# Kernal2.net
KiCad netlist of a schematic drawn in Altium Designer
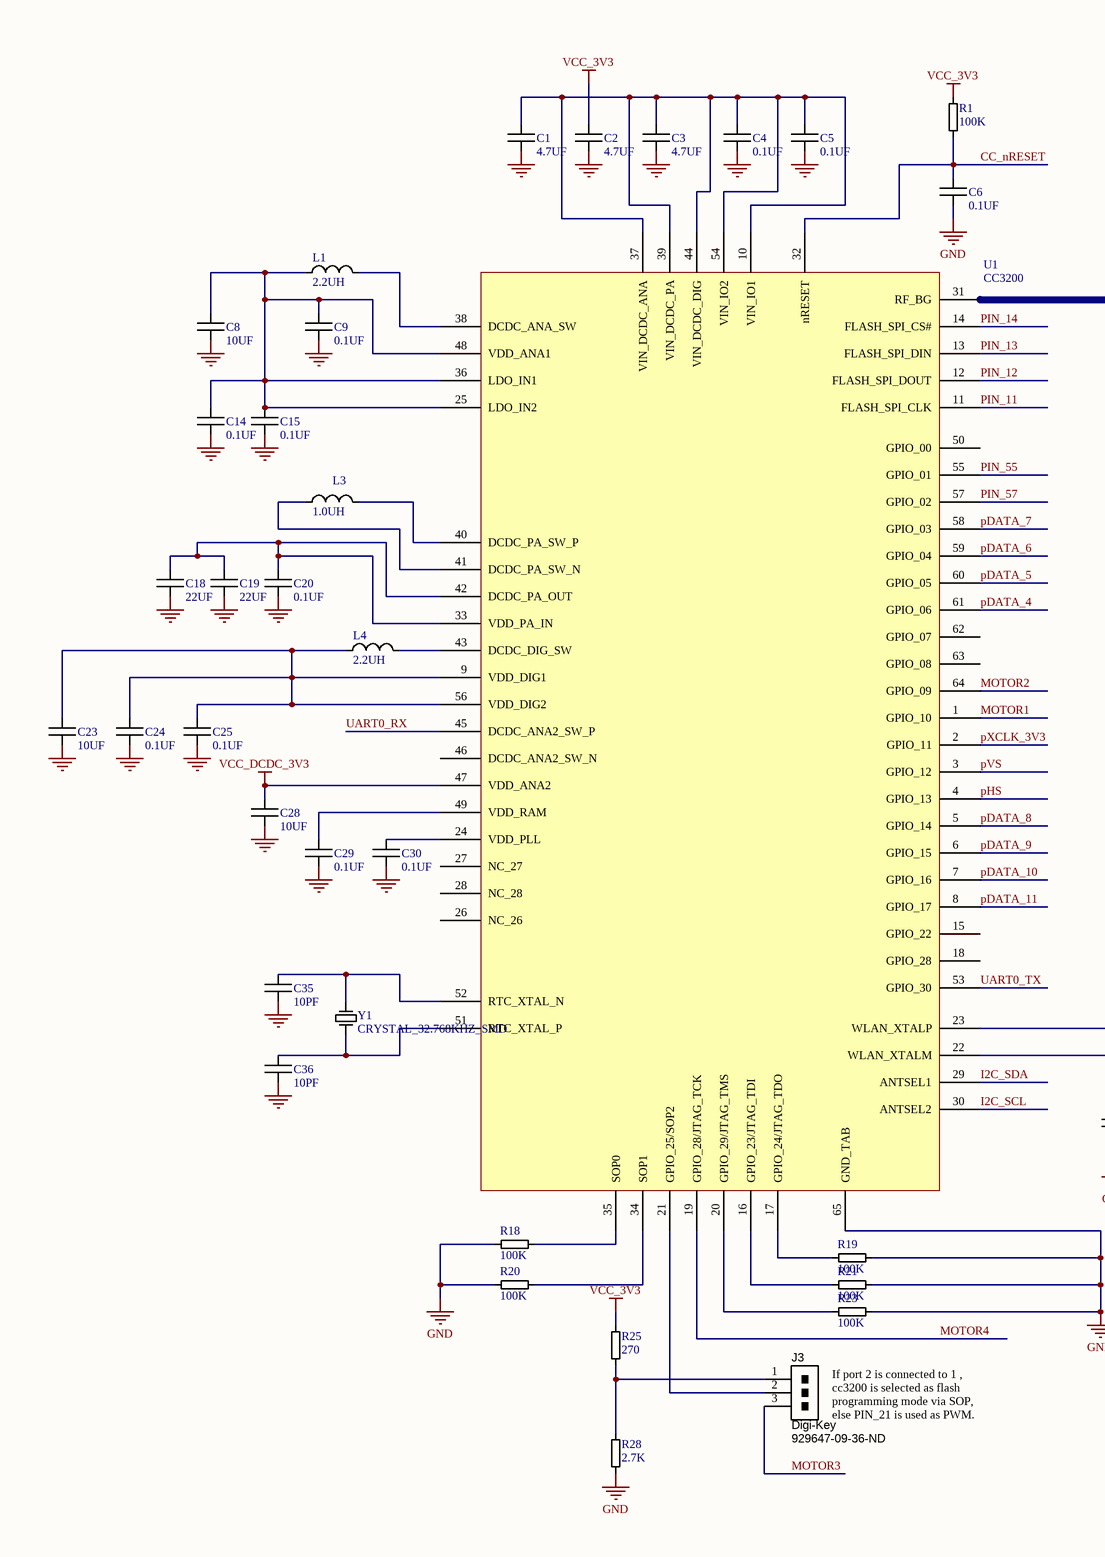
[diagram p0: Kernal2.SchDoc, left]
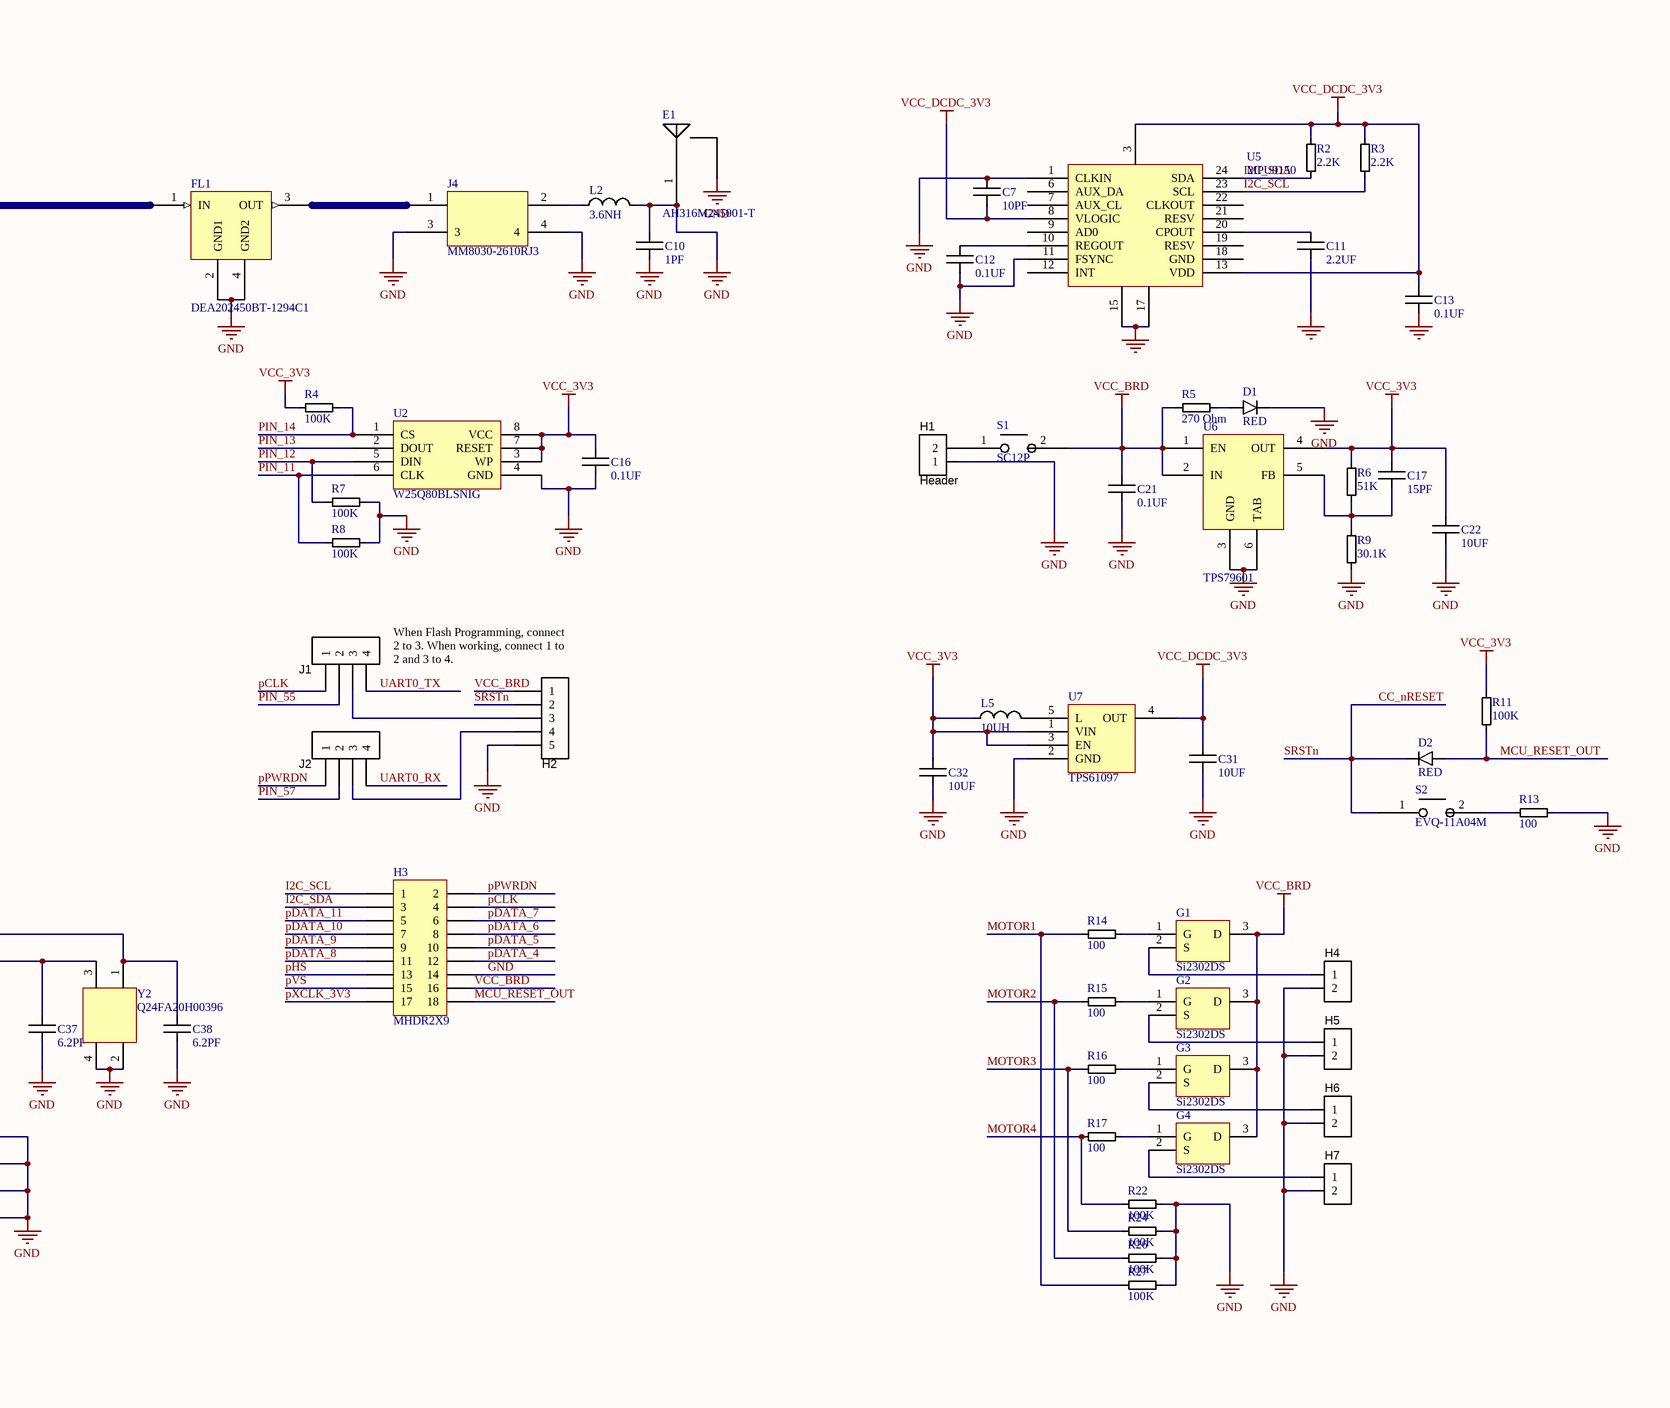
[diagram p1: Kernal2.SchDoc, right]

(export (version "E")
  (design (tool "Eeschema 10.0.6"))
  (components
    (comp (ref "C1")
      (value "4.7UF")
      (footprint "0402")
      (description "CAP CER 4.7UF 6.3V 20% X5R 0402")
      (libsource (lib "FuzzyWasp") (part "CAP_0402"))
    )
    (comp (ref "C2") (value "4.7UF") (footprint "0402") (libsource (lib "FuzzyWasp") (part "CAP_0402")))
    (comp (ref "C3") (value "4.7UF") (footprint "0402") (libsource (lib "FuzzyWasp") (part "CAP_0402")))
    (comp (ref "C4")
      (value "0.1UF")
      (footprint "0402")
      (description "CAP CER 0.1UF 10V 10% X5R 0402")
      (libsource (lib "FuzzyWasp") (part "CAP_0402"))
    )
    (comp (ref "C5")
      (value "0.1UF")
      (footprint "0402")
      (description "CAP CER 0.1UF 10V 10% X5R 0402")
      (libsource (lib "FuzzyWasp") (part "CAP_0402"))
    )
    (comp (ref "C6")
      (value "0.1UF")
      (footprint "0402")
      (description "CAP CER 0.1UF 10V 10% X5R 0402")
      (libsource (lib "FuzzyWasp") (part "CAP_0402"))
    )
    (comp (ref "C7")
      (value "10PF")
      (footprint "0402")
      (description "CAP CER 10PF 50V NP0 0402")
      (libsource (lib "FuzzyWasp") (part "CAP_0402"))
    )
    (comp (ref "C8")
      (value "10UF")
      (footprint "0402")
      (description "CAP CER 10UF 6.3V 20% X5R 0603")
      (libsource (lib "FuzzyWasp") (part "CAP_0402"))
    )
    (comp (ref "C9")
      (value "0.1UF")
      (footprint "0402")
      (description "CAP CER 0.1UF 10V 10% X5R 0402")
      (libsource (lib "FuzzyWasp") (part "CAP_0402"))
    )
    (comp (ref "C10")
      (value "1PF")
      (footprint "0402")
      (description "CAP CER 1PF 50V NP0 0402")
      (libsource (lib "FuzzyWasp") (part "CAP_0402"))
    )
    (comp (ref "C11")
      (value "2.2UF")
      (footprint "0402")
      (description "CAP CER 2.2UF 10V 10% X5R 0402")
      (libsource (lib "FuzzyWasp") (part "CAP_0402"))
    )
    (comp (ref "C12")
      (value "0.1UF")
      (footprint "0402")
      (description "CAP CER 0.1UF 10V 10% X5R 0402")
      (libsource (lib "FuzzyWasp") (part "CAP_0402"))
    )
    (comp (ref "C13")
      (value "0.1UF")
      (footprint "0402")
      (description "CAP CER 0.1UF 10V 10% X5R 0402")
      (libsource (lib "FuzzyWasp") (part "CAP_0402"))
    )
    (comp (ref "C14")
      (value "0.1UF")
      (footprint "0402")
      (description "CAP CER 0.1UF 10V 10% X5R 0402")
      (libsource (lib "FuzzyWasp") (part "CAP_0402"))
    )
    (comp (ref "C15")
      (value "0.1UF")
      (footprint "0402")
      (description "CAP CER 0.1UF 10V 10% X5R 0402")
      (libsource (lib "FuzzyWasp") (part "CAP_0402"))
    )
    (comp (ref "C16")
      (value "0.1UF")
      (footprint "0402")
      (description "CAP CER 0.1UF 10V 10% X5R 0402")
      (libsource (lib "FuzzyWasp") (part "CAP_0402"))
    )
    (comp (ref "C17")
      (value "15PF")
      (footprint "0402")
      (description "CAP CER 15PF 50V 5% NP0 0402")
      (libsource (lib "FuzzyWasp") (part "CAP_0402"))
    )
    (comp (ref "C18")
      (value "22UF")
      (footprint "0603")
      (description "CAP CER 22UF 4V 20% X5R 0603")
      (libsource (lib "FuzzyWasp") (part "CAP_0603"))
    )
    (comp (ref "C19")
      (value "22UF")
      (footprint "0603")
      (description "CAP CER 22UF 4V 20% X5R 0603")
      (libsource (lib "FuzzyWasp") (part "CAP_0603"))
    )
    (comp (ref "C20")
      (value "0.1UF")
      (footprint "0402")
      (description "CAP CER 0.1UF 10V 10% X5R 0402")
      (libsource (lib "FuzzyWasp") (part "CAP_0402"))
    )
    (comp (ref "C21")
      (value "0.1UF")
      (footprint "0402")
      (description "CAP CER 0.1UF 10V 10% X5R 0402")
      (libsource (lib "FuzzyWasp") (part "CAP_0402"))
    )
    (comp (ref "C22")
      (value "10UF")
      (footprint "0805")
      (description "CAP CER 10UF 10V 10% X5R 0805")
      (libsource (lib "FuzzyWasp") (part "CAP_0805"))
    )
    (comp (ref "C23")
      (value "10UF")
      (footprint "0603")
      (description "CAP CER 10UF 6.3V 20% X5R 0603")
      (libsource (lib "FuzzyWasp") (part "CAP_0603"))
    )
    (comp (ref "C24")
      (value "0.1UF")
      (footprint "0402")
      (description "CAP CER 0.1UF 10V 10% X5R 0402")
      (libsource (lib "FuzzyWasp") (part "CAP_0402"))
    )
    (comp (ref "C25")
      (value "0.1UF")
      (footprint "0402")
      (description "CAP CER 0.1UF 10V 10% X5R 0402")
      (libsource (lib "FuzzyWasp") (part "CAP_0402"))
    )
    (comp (ref "C28")
      (value "10UF")
      (footprint "0603")
      (description "CAP CER 10UF 6.3V 20% X5R 0603")
      (libsource (lib "FuzzyWasp") (part "CAP_0603"))
    )
    (comp (ref "C29")
      (value "0.1UF")
      (footprint "0402")
      (description "CAP CER 0.1UF 10V 10% X5R 0402")
      (libsource (lib "FuzzyWasp") (part "CAP_0402"))
    )
    (comp (ref "C30")
      (value "0.1UF")
      (footprint "0402")
      (description "CAP CER 0.1UF 10V 10% X5R 0402")
      (libsource (lib "FuzzyWasp") (part "CAP_0402"))
    )
    (comp (ref "C31")
      (value "10UF")
      (footprint "0603")
      (description "CAP CER 10UF 6.3V 20% X5R 0603")
      (libsource (lib "FuzzyWasp") (part "CAP_0603"))
    )
    (comp (ref "C32")
      (value "10UF")
      (footprint "0603")
      (description "CAP CER 10UF 6.3V 20% X5R 0603")
      (libsource (lib "FuzzyWasp") (part "CAP_0603"))
    )
    (comp (ref "C35")
      (value "10PF")
      (footprint "0402")
      (description "CAP CER 10PF 50V 1% NP0 0402")
      (libsource (lib "FuzzyWasp") (part "CAP_0402"))
    )
    (comp (ref "C36")
      (value "10PF")
      (footprint "0402")
      (description "CAP CER 10PF 50V 1% NP0 0402")
      (libsource (lib "FuzzyWasp") (part "CAP_0402"))
    )
    (comp (ref "C37")
      (value "6.2PF")
      (footprint "0402")
      (description "CAP CER 6.2PF 50V NP0 0402")
      (libsource (lib "FuzzyWasp") (part "CAP_0402"))
    )
    (comp (ref "C38")
      (value "6.2PF")
      (footprint "0402")
      (description "CAP CER 6.2PF 50V NP0 0402")
      (libsource (lib "FuzzyWasp") (part "CAP_0402"))
    )
    (comp (ref "D1")
      (value "RED")
      (footprint "0603")
      (description "LED CHIPLED 633NM RED 0603 SMD")
      (libsource (lib "FuzzyWasp") (part "LED_0603"))
    )
    (comp (ref "D2")
      (value "RED")
      (footprint "0603")
      (description "LED CHIPLED 633NM RED 0603 SMD")
      (libsource (lib "FuzzyWasp") (part "LED_0603"))
    )
    (comp (ref "E1")
      (value "AH316M245001-T")
      (footprint "AH316M245001-T")
      (libsource (lib "FuzzyWasp-2") (part "AH316M245001-T"))
    )
    (comp (ref "FL1")
      (value "DEA202450BT-1294C1")
      (footprint "DEA202450BT-1294C1-H")
      (libsource (lib "FuzzyWasp-2") (part "DEA202450BT-1294C1"))
    )
    (comp (ref "G1")
      (value "Si2302DS")
      (footprint "Si2302DS")
      (libsource (lib "FuzzyWasp-2") (part "Si2302DS"))
    )
    (comp (ref "G2")
      (value "Si2302DS")
      (footprint "Si2302DS")
      (libsource (lib "FuzzyWasp-2") (part "Si2302DS"))
    )
    (comp (ref "G3")
      (value "Si2302DS")
      (footprint "Si2302DS")
      (libsource (lib "FuzzyWasp-2") (part "Si2302DS"))
    )
    (comp (ref "G4")
      (value "Si2302DS")
      (footprint "Si2302DS")
      (libsource (lib "FuzzyWasp-2") (part "Si2302DS"))
    )
    (comp (ref "H1")
      (value "Header")
      (footprint "MHDR1X2")
      (description "Header, 2-pin")
      (libsource (lib "PBL - Connectors") (part "Header2P"))
    )
    (comp (ref "H2")
      (value "Programmer")
      (footprint "MHDR1X5")
      (description "Header 5-pin")
      (libsource (lib "PBL - Connectors") (part "Header5P"))
    )
    (comp (ref "H3")
      (value "MHDR2X9")
      (footprint "MHDR2X9")
      (description "Header, 9-Pin, Dual row")
      (fields (field (name "PUBLISHER") "Altium Limited"))
      (libsource (lib "Miscellaneous Connectors") (part "MHDR2X9"))
    )
    (comp (ref "H4")
      (value "Header")
      (footprint "MHDR1X2")
      (description "Header, 2-pin")
      (libsource (lib "") (part "Header2P_1"))
    )
    (comp (ref "H5")
      (value "Header")
      (footprint "MHDR1X2")
      (description "Header, 2-pin")
      (libsource (lib "") (part "Header2P_1"))
    )
    (comp (ref "H6")
      (value "Header")
      (footprint "MHDR1X2")
      (description "Header, 2-pin")
      (libsource (lib "") (part "Header2P_1"))
    )
    (comp (ref "H7")
      (value "Header")
      (footprint "MHDR1X2")
      (description "Header, 2-pin")
      (libsource (lib "") (part "Header2P_1"))
    )
    (comp (ref "J1")
      (value "Programmer")
      (footprint "MHDR1X4")
      (description "Header 4-pin")
      (libsource (lib "PBL - Connectors") (part "Header4P"))
    )
    (comp (ref "J2")
      (value "Programmer")
      (footprint "MHDR1X4")
      (description "Header 4-pin")
      (libsource (lib "PBL - Connectors") (part "Header4P"))
    )
    (comp (ref "J3")
      (value "CONN_HEADER_1x3P_0.100in")
      (footprint "MHDR1X3")
      (description "Pin Header, THT, Single-row, 2.54mm pitch")
      (fields
        (field (name "SUPPLIER 1") "Digi-Key")
        (field (name "SUPPLIER PART NUMBER 1") "929647-09-36-ND")
      )
      (libsource (lib "PBL - Connectors") (part "CONN_HEADER_1x3P_0.100in"))
    )
    (comp (ref "J4")
      (value "MM8030-2610RJ3")
      (footprint "MM8030-2610RJ3")
      (libsource (lib "FuzzyWasp-2") (part "MM8030-2610RJ3"))
    )
    (comp (ref "L1")
      (value "2.2UH")
      (footprint "1008")
      (description "INDUCTOR 2.2UH 20% 1300MA 1008")
      (libsource (lib "FuzzyWasp") (part "INDUCTOR_1008"))
    )
    (comp (ref "L2")
      (value "3.6NH")
      (footprint "0402")
      (description "INDUCTOR 3.6NH 0.1NH 0402")
      (libsource (lib "FuzzyWasp") (part "INDUCTOR_0402"))
    )
    (comp (ref "L3")
      (value "1.0UH")
      (footprint "1007")
      (description "INDUCTOR POWER 1.0UH 1007")
      (libsource (lib "FuzzyWasp") (part "INDUCTOR_1007"))
    )
    (comp (ref "L4")
      (value "2.2UH")
      (footprint "1008")
      (description "INDUCTOR 2.2UH 20% 1300MA 1008")
      (libsource (lib "FuzzyWasp") (part "INDUCTOR_1008"))
    )
    (comp (ref "L5")
      (value "10UH")
      (footprint "1007")
      (description "INDUCTOR POWER 10UH 1007")
      (libsource (lib "FuzzyWasp") (part "INDUCTOR_1007"))
    )
    (comp (ref "R1")
      (value "100K")
      (footprint "0402")
      (description "RES 100K OHM 1/16W 5% 0402 SMD")
      (libsource (lib "FuzzyWasp") (part "RES_0402"))
    )
    (comp (ref "R2")
      (value "2.2K")
      (footprint "0402")
      (description "RES 2.2K OHM 1/10W 5% 0402 SMD")
      (libsource (lib "FuzzyWasp") (part "RES_0402"))
    )
    (comp (ref "R3")
      (value "2.2K")
      (footprint "0402")
      (description "RES 2.2K OHM 1/10W 5% 0402 SMD")
      (libsource (lib "FuzzyWasp") (part "RES_0402"))
    )
    (comp (ref "R4")
      (value "100K")
      (footprint "0402")
      (description "RES 100K OHM 1/16W 5% 0402 SMD")
      (libsource (lib "FuzzyWasp") (part "RES_0402"))
    )
    (comp (ref "R5")
      (value "270 Ohm")
      (footprint "0402")
      (description "RES 270 OHM 1/10W 5% 0603 SMD")
      (libsource (lib "FuzzyWasp") (part "RES_0402"))
    )
    (comp (ref "R6")
      (value "51K")
      (footprint "0402")
      (description "RES 51K OHM 1/16W 1% 0402")
      (libsource (lib "FuzzyWasp") (part "RES_0402"))
    )
    (comp (ref "R7")
      (value "100K")
      (footprint "0402")
      (description "RES 100K OHM 1/16W 5% 0402 SMD")
      (libsource (lib "FuzzyWasp") (part "RES_0402"))
    )
    (comp (ref "R8")
      (value "100K")
      (footprint "0402")
      (description "RES 100K OHM 1/16W 5% 0402 SMD")
      (libsource (lib "FuzzyWasp") (part "RES_0402"))
    )
    (comp (ref "R9")
      (value "30.1K")
      (footprint "0402")
      (description "RES 30.1K OHM 1/16W 1% 0402 SMD")
      (libsource (lib "FuzzyWasp") (part "RES_0402"))
    )
    (comp (ref "R11")
      (value "100K")
      (footprint "0402")
      (description "RES 100K OHM 1/16W 5% 0402 SMD")
      (libsource (lib "FuzzyWasp") (part "RES_0402"))
    )
    (comp (ref "R13")
      (value "100")
      (footprint "0402")
      (description "RES 100 OHM 1/10W 5% 0402 SMD")
      (libsource (lib "FuzzyWasp") (part "RES_0402"))
    )
    (comp (ref "R14")
      (value "100")
      (footprint "0402")
      (description "RES 100 OHM 1/10W 5% 0402 SMD")
      (libsource (lib "FuzzyWasp") (part "RES_0402"))
    )
    (comp (ref "R15")
      (value "100")
      (footprint "0402")
      (description "RES 100 OHM 1/10W 5% 0402 SMD")
      (libsource (lib "FuzzyWasp") (part "RES_0402"))
    )
    (comp (ref "R16")
      (value "100")
      (footprint "0402")
      (description "RES 100 OHM 1/10W 5% 0402 SMD")
      (libsource (lib "FuzzyWasp") (part "RES_0402"))
    )
    (comp (ref "R17")
      (value "100")
      (footprint "0402")
      (description "RES 100 OHM 1/10W 5% 0402 SMD")
      (libsource (lib "FuzzyWasp") (part "RES_0402"))
    )
    (comp (ref "R18")
      (value "100K")
      (footprint "0402")
      (description "RES 100K OHM 1/16W 5% 0402 SMD")
      (libsource (lib "FuzzyWasp") (part "RES_0402"))
    )
    (comp (ref "R19")
      (value "100K")
      (footprint "0402")
      (description "RES 100K OHM 1/16W 5% 0402 SMD")
      (libsource (lib "FuzzyWasp") (part "RES_0402"))
    )
    (comp (ref "R20")
      (value "100K")
      (footprint "0402")
      (description "RES 100K OHM 1/16W 5% 0402 SMD")
      (libsource (lib "FuzzyWasp") (part "RES_0402"))
    )
    (comp (ref "R21")
      (value "100K")
      (footprint "0402")
      (description "RES 100K OHM 1/16W 5% 0402 SMD")
      (libsource (lib "FuzzyWasp") (part "RES_0402"))
    )
    (comp (ref "R22")
      (value "100K")
      (footprint "0402")
      (description "RES 100K OHM 1/16W 5% 0402 SMD")
      (libsource (lib "FuzzyWasp") (part "RES_0402"))
    )
    (comp (ref "R23")
      (value "100K")
      (footprint "0402")
      (description "RES 100K OHM 1/16W 5% 0402 SMD")
      (libsource (lib "FuzzyWasp") (part "RES_0402"))
    )
    (comp (ref "R24")
      (value "100K")
      (footprint "0402")
      (description "RES 100K OHM 1/16W 5% 0402 SMD")
      (libsource (lib "FuzzyWasp") (part "RES_0402"))
    )
    (comp (ref "R25")
      (value "270")
      (footprint "0402")
      (description "RES 270 OHM 1/16W 1% 0402 SMD")
      (libsource (lib "FuzzyWasp") (part "RES_0402"))
    )
    (comp (ref "R26")
      (value "100K")
      (footprint "0402")
      (description "RES 100K OHM 1/16W 5% 0402 SMD")
      (libsource (lib "FuzzyWasp") (part "RES_0402"))
    )
    (comp (ref "R27")
      (value "100K")
      (footprint "0402")
      (description "RES 100K OHM 1/16W 5% 0402 SMD")
      (libsource (lib "FuzzyWasp") (part "RES_0402"))
    )
    (comp (ref "R28")
      (value "2.7K")
      (footprint "0402")
      (description "RES 2.70K OHM 1/16W 1% 0402 SMD")
      (libsource (lib "FuzzyWasp") (part "RES_0402"))
    )
    (comp (ref "S1") (value "SC12P") (footprint "SC12P") (libsource (lib "FuzzyWasp") (part "SC12P")))
    (comp (ref "S2")
      (value "EVQ-11A04M")
      (footprint "EVQ-11")
      (libsource (lib "FuzzyWasp") (part "EVQ-11A04M"))
    )
    (comp (ref "U1") (value "CC3200") (footprint "CC3200") (libsource (lib "FuzzyWasp-2") (part "CC3200")))
    (comp (ref "U2")
      (value "W25Q80BLSNIG")
      (footprint "W25Q80BLSNIG")
      (libsource (lib "FuzzyWasp-2") (part "W25Q80BLSNIG"))
    )
    (comp (ref "U5") (value "MPU9150") (footprint "MPU9150") (libsource (lib "FuzzyWasp-2") (part "MPU9150")))
    (comp (ref "U6")
      (value "TPS79601")
      (footprint "TPS79601")
      (libsource (lib "FuzzyWasp-2") (part "TPS79601"))
    )
    (comp (ref "U7")
      (value "TPS61097")
      (footprint "TPS61097A-33")
      (libsource (lib "FuzzyWasp-2") (part "TPS61097"))
    )
    (comp (ref "Y1")
      (value "CRYSTAL_32.768KHZ_SMD")
      (footprint "ABS07")
      (libsource (lib "FuzzyWasp-2") (part "CRYSTAL_32.768KHZ_SMD"))
    )
    (comp (ref "Y2") (value "Q24FA20H00396") (libsource (lib "FuzzyWasp-2") (part "Q24FA20H00396")))
  )
  (nets
    (net (code "1") (name "/CC_nRESET") (class "Default")
      (node (ref "C6") (pin "2") (pinfunction "2_2") (pintype "passive"))
      (node (ref "D2") (pin "2") (pinfunction "2_2") (pintype "passive"))
      (node (ref "H2") (pin "2") (pinfunction "2_2") (pintype "passive"))
      (node (ref "R1") (pin "1") (pinfunction "1_1") (pintype "passive"))
      (node (ref "S2") (pin "1") (pinfunction "1_1") (pintype "passive"))
      (node (ref "U1") (pin "32") (pinfunction "nRESET_32") (pintype "passive"))
    )
    (net (code "2") (name "/I2C_SCL") (class "Default")
      (node (ref "H3") (pin "1") (pinfunction "1_1") (pintype "passive"))
      (node (ref "R3") (pin "1") (pinfunction "1_1") (pintype "passive"))
      (node (ref "U1") (pin "30") (pinfunction "ANTSEL2_30") (pintype "passive"))
      (node (ref "U5") (pin "23") (pinfunction "SCL_23") (pintype "passive"))
    )
    (net (code "3") (name "/I2C_SDA") (class "Default")
      (node (ref "H3") (pin "3") (pinfunction "3_3") (pintype "passive"))
      (node (ref "R2") (pin "1") (pinfunction "1_1") (pintype "passive"))
      (node (ref "U1") (pin "29") (pinfunction "ANTSEL1_29") (pintype "passive"))
      (node (ref "U5") (pin "24") (pinfunction "SDA_24") (pintype "passive"))
    )
    (net (code "4") (name "/MCU_RESET_OUT") (class "Default")
      (node (ref "D2") (pin "1") (pinfunction "1_1") (pintype "passive"))
      (node (ref "H3") (pin "18") (pinfunction "18_18") (pintype "passive"))
      (node (ref "R11") (pin "1") (pinfunction "1_1") (pintype "passive"))
    )
    (net (code "5") (name "/MOTOR1") (class "Default")
      (node (ref "R14") (pin "1") (pinfunction "1_1") (pintype "passive"))
      (node (ref "R27") (pin "1") (pinfunction "1_1") (pintype "passive"))
      (node (ref "U1") (pin "1") (pinfunction "GPIO_10_1") (pintype "passive"))
    )
    (net (code "6") (name "/MOTOR2") (class "Default")
      (node (ref "R15") (pin "1") (pinfunction "1_1") (pintype "passive"))
      (node (ref "R26") (pin "1") (pinfunction "1_1") (pintype "passive"))
      (node (ref "U1") (pin "64") (pinfunction "GPIO_09_64") (pintype "passive"))
    )
    (net (code "7") (name "/MOTOR3") (class "Default")
      (node (ref "J3") (pin "3") (pinfunction "3_3") (pintype "passive"))
      (node (ref "R16") (pin "1") (pinfunction "1_1") (pintype "passive"))
      (node (ref "R24") (pin "1") (pinfunction "1_1") (pintype "passive"))
    )
    (net (code "8") (name "/MOTOR4") (class "Default")
      (node (ref "R17") (pin "1") (pinfunction "1_1") (pintype "passive"))
      (node (ref "R22") (pin "1") (pinfunction "1_1") (pintype "passive"))
      (node (ref "U1") (pin "19") (pinfunction "GPIO_28/JTAG_TCK_19") (pintype "passive"))
    )
    (net (code "9") (name "/PIN_11") (class "Default")
      (node (ref "R8") (pin "1") (pinfunction "1_1") (pintype "passive"))
      (node (ref "U1") (pin "11") (pinfunction "FLASH_SPI_CLK_11") (pintype "passive"))
      (node (ref "U2") (pin "6") (pinfunction "CLK_6") (pintype "passive"))
    )
    (net (code "10") (name "/PIN_12") (class "Default")
      (node (ref "R7") (pin "1") (pinfunction "1_1") (pintype "passive"))
      (node (ref "U1") (pin "12") (pinfunction "FLASH_SPI_DOUT_12") (pintype "passive"))
      (node (ref "U2") (pin "5") (pinfunction "DIN_5") (pintype "passive"))
    )
    (net (code "11") (name "/PIN_13") (class "Default")
      (node (ref "U1") (pin "13") (pinfunction "FLASH_SPI_DIN_13") (pintype "passive"))
      (node (ref "U2") (pin "2") (pinfunction "DOUT_2") (pintype "passive"))
    )
    (net (code "12") (name "/PIN_14") (class "Default")
      (node (ref "R4") (pin "2") (pinfunction "2_2") (pintype "passive"))
      (node (ref "U1") (pin "14") (pinfunction "FLASH_SPI_CS#_14") (pintype "passive"))
      (node (ref "U2") (pin "1") (pinfunction "CS_1") (pintype "passive"))
    )
    (net (code "13") (name "/PIN_55") (class "Default")
      (node (ref "J1") (pin "2") (pinfunction "2_2") (pintype "passive"))
      (node (ref "U1") (pin "55") (pinfunction "GPIO_01_55") (pintype "passive"))
    )
    (net (code "14") (name "/PIN_57") (class "Default")
      (node (ref "J2") (pin "2") (pinfunction "2_2") (pintype "passive"))
      (node (ref "U1") (pin "57") (pinfunction "GPIO_02_57") (pintype "passive"))
    )
    (net (code "15") (name "/UART0_RX") (class "Default")
      (node (ref "J2") (pin "4") (pinfunction "4_4") (pintype "passive"))
      (node (ref "U1") (pin "45") (pinfunction "DCDC_ANA2_SW_P_45") (pintype "passive"))
    )
    (net (code "16") (name "/UART0_TX") (class "Default")
      (node (ref "J1") (pin "4") (pinfunction "4_4") (pintype "passive"))
      (node (ref "U1") (pin "53") (pinfunction "GPIO_30_53") (pintype "passive"))
    )
    (net (code "17") (name "/pCLK") (class "Default")
      (node (ref "H3") (pin "4") (pinfunction "4_4") (pintype "passive"))
      (node (ref "J1") (pin "1") (pinfunction "1_1") (pintype "passive"))
    )
    (net (code "18") (name "/pDATA_4") (class "Default")
      (node (ref "H3") (pin "12") (pinfunction "12_12") (pintype "passive"))
      (node (ref "U1") (pin "61") (pinfunction "GPIO_06_61") (pintype "passive"))
    )
    (net (code "19") (name "/pDATA_5") (class "Default")
      (node (ref "H3") (pin "10") (pinfunction "10_10") (pintype "passive"))
      (node (ref "U1") (pin "60") (pinfunction "GPIO_05_60") (pintype "passive"))
    )
    (net (code "20") (name "/pDATA_6") (class "Default")
      (node (ref "H3") (pin "8") (pinfunction "8_8") (pintype "passive"))
      (node (ref "U1") (pin "59") (pinfunction "GPIO_04_59") (pintype "passive"))
    )
    (net (code "21") (name "/pDATA_7") (class "Default")
      (node (ref "H3") (pin "6") (pinfunction "6_6") (pintype "passive"))
      (node (ref "U1") (pin "58") (pinfunction "GPIO_03_58") (pintype "passive"))
    )
    (net (code "22") (name "/pDATA_8") (class "Default")
      (node (ref "H3") (pin "11") (pinfunction "11_11") (pintype "passive"))
      (node (ref "U1") (pin "5") (pinfunction "GPIO_14_5") (pintype "passive"))
    )
    (net (code "23") (name "/pDATA_9") (class "Default")
      (node (ref "H3") (pin "9") (pinfunction "9_9") (pintype "passive"))
      (node (ref "U1") (pin "6") (pinfunction "GPIO_15_6") (pintype "passive"))
    )
    (net (code "24") (name "/pDATA_10") (class "Default")
      (node (ref "H3") (pin "7") (pinfunction "7_7") (pintype "passive"))
      (node (ref "U1") (pin "7") (pinfunction "GPIO_16_7") (pintype "passive"))
    )
    (net (code "25") (name "/pDATA_11") (class "Default")
      (node (ref "H3") (pin "5") (pinfunction "5_5") (pintype "passive"))
      (node (ref "U1") (pin "8") (pinfunction "GPIO_17_8") (pintype "passive"))
    )
    (net (code "26") (name "/pHS") (class "Default")
      (node (ref "H3") (pin "13") (pinfunction "13_13") (pintype "passive"))
      (node (ref "U1") (pin "4") (pinfunction "GPIO_13_4") (pintype "passive"))
    )
    (net (code "27") (name "/pPWRDN") (class "Default")
      (node (ref "H3") (pin "2") (pinfunction "2_2") (pintype "passive"))
      (node (ref "J2") (pin "1") (pinfunction "1_1") (pintype "passive"))
    )
    (net (code "28") (name "/pVS") (class "Default")
      (node (ref "H3") (pin "15") (pinfunction "15_15") (pintype "passive"))
      (node (ref "U1") (pin "3") (pinfunction "GPIO_12_3") (pintype "passive"))
    )
    (net (code "29") (name "/pXCLK_3V3") (class "Default")
      (node (ref "H3") (pin "17") (pinfunction "17_17") (pintype "passive"))
      (node (ref "U1") (pin "2") (pinfunction "GPIO_11_2") (pintype "passive"))
    )
    (net (code "30") (name "GND") (class "Default")
      (node (ref "C1") (pin "1") (pinfunction "1_1") (pintype "passive"))
      (node (ref "C10") (pin "1") (pinfunction "1_1") (pintype "passive"))
      (node (ref "C10") (pin "2") (pinfunction "2_2") (pintype "passive"))
      (node (ref "C11") (pin "1") (pinfunction "1_1") (pintype "passive"))
      (node (ref "C12") (pin "1") (pinfunction "1_1") (pintype "passive"))
      (node (ref "C13") (pin "1") (pinfunction "1_1") (pintype "passive"))
      (node (ref "C14") (pin "1") (pinfunction "1_1") (pintype "passive"))
      (node (ref "C15") (pin "1") (pinfunction "1_1") (pintype "passive"))
      (node (ref "C16") (pin "1") (pinfunction "1_1") (pintype "passive"))
      (node (ref "C18") (pin "1") (pinfunction "1_1") (pintype "passive"))
      (node (ref "C19") (pin "1") (pinfunction "1_1") (pintype "passive"))
      (node (ref "C2") (pin "1") (pinfunction "1_1") (pintype "passive"))
      (node (ref "C20") (pin "1") (pinfunction "1_1") (pintype "passive"))
      (node (ref "C21") (pin "1") (pinfunction "1_1") (pintype "passive"))
      (node (ref "C22") (pin "1") (pinfunction "1_1") (pintype "passive"))
      (node (ref "C23") (pin "1") (pinfunction "1_1") (pintype "passive"))
      (node (ref "C24") (pin "1") (pinfunction "1_1") (pintype "passive"))
      (node (ref "C25") (pin "1") (pinfunction "1_1") (pintype "passive"))
      (node (ref "C28") (pin "1") (pinfunction "1_1") (pintype "passive"))
      (node (ref "C29") (pin "1") (pinfunction "1_1") (pintype "passive"))
      (node (ref "C3") (pin "1") (pinfunction "1_1") (pintype "passive"))
      (node (ref "C30") (pin "1") (pinfunction "1_1") (pintype "passive"))
      (node (ref "C31") (pin "1") (pinfunction "1_1") (pintype "passive"))
      (node (ref "C32") (pin "1") (pinfunction "1_1") (pintype "passive"))
      (node (ref "C35") (pin "1") (pinfunction "1_1") (pintype "passive"))
      (node (ref "C36") (pin "1") (pinfunction "1_1") (pintype "passive"))
      (node (ref "C37") (pin "1") (pinfunction "1_1") (pintype "passive"))
      (node (ref "C38") (pin "1") (pinfunction "1_1") (pintype "passive"))
      (node (ref "C4") (pin "1") (pinfunction "1_1") (pintype "passive"))
      (node (ref "C5") (pin "1") (pinfunction "1_1") (pintype "passive"))
      (node (ref "C6") (pin "1") (pinfunction "1_1") (pintype "passive"))
      (node (ref "C7") (pin "2") (pinfunction "2_2") (pintype "passive"))
      (node (ref "C8") (pin "1") (pinfunction "1_1") (pintype "passive"))
      (node (ref "C9") (pin "1") (pinfunction "1_1") (pintype "passive"))
      (node (ref "D1") (pin "2") (pinfunction "2_2") (pintype "passive"))
      (node (ref "E1") (pin "1") (pinfunction "Feed_1") (pintype "passive"))
      (node (ref "E1") (pin "2") (pinfunction "GND_2") (pintype "passive"))
      (node (ref "FL1") (pin "2") (pinfunction "GND1_2") (pintype "passive"))
      (node (ref "FL1") (pin "4") (pinfunction "GND2_4") (pintype "passive"))
      (node (ref "H1") (pin "1") (pinfunction "1_1") (pintype "passive"))
      (node (ref "H2") (pin "5") (pinfunction "5_5") (pintype "passive"))
      (node (ref "H3") (pin "14") (pinfunction "14_14") (pintype "passive"))
      (node (ref "H4") (pin "2") (pinfunction "2_2") (pintype "passive"))
      (node (ref "H5") (pin "2") (pinfunction "2_2") (pintype "passive"))
      (node (ref "H6") (pin "2") (pinfunction "2_2") (pintype "passive"))
      (node (ref "H7") (pin "2") (pinfunction "2_2") (pintype "passive"))
      (node (ref "J4") (pin "3") (pinfunction "3_3") (pintype "passive"))
      (node (ref "J4") (pin "4") (pinfunction "4_4") (pintype "passive"))
      (node (ref "L2") (pin "1") (pinfunction "1_1") (pintype "passive"))
      (node (ref "R13") (pin "2") (pinfunction "2_2") (pintype "passive"))
      (node (ref "R18") (pin "1") (pinfunction "1_1") (pintype "passive"))
      (node (ref "R19") (pin "2") (pinfunction "2_2") (pintype "passive"))
      (node (ref "R20") (pin "1") (pinfunction "1_1") (pintype "passive"))
      (node (ref "R21") (pin "2") (pinfunction "2_2") (pintype "passive"))
      (node (ref "R22") (pin "2") (pinfunction "2_2") (pintype "passive"))
      (node (ref "R23") (pin "2") (pinfunction "2_2") (pintype "passive"))
      (node (ref "R24") (pin "2") (pinfunction "2_2") (pintype "passive"))
      (node (ref "R26") (pin "2") (pinfunction "2_2") (pintype "passive"))
      (node (ref "R27") (pin "2") (pinfunction "2_2") (pintype "passive"))
      (node (ref "R28") (pin "1") (pinfunction "1_1") (pintype "passive"))
      (node (ref "R7") (pin "2") (pinfunction "2_2") (pintype "passive"))
      (node (ref "R8") (pin "2") (pinfunction "2_2") (pintype "passive"))
      (node (ref "R9") (pin "1") (pinfunction "1_1") (pintype "passive"))
      (node (ref "U1") (pin "65") (pinfunction "GND_TAB_65") (pintype "passive"))
      (node (ref "U2") (pin "4") (pinfunction "GND_4") (pintype "passive"))
      (node (ref "U5") (pin "1") (pinfunction "CLKIN_1") (pintype "passive"))
      (node (ref "U5") (pin "11") (pinfunction "FSYNC_11") (pintype "passive"))
      (node (ref "U5") (pin "15") (pintype "passive"))
      (node (ref "U5") (pin "17") (pintype "passive"))
      (node (ref "U6") (pin "3") (pinfunction "GND_3") (pintype "passive"))
      (node (ref "U6") (pin "6") (pinfunction "TAB_6") (pintype "passive"))
      (node (ref "U7") (pin "2") (pinfunction "GND_2") (pintype "passive"))
      (node (ref "Y2") (pin "2") (pinfunction "2_2") (pintype "passive"))
      (node (ref "Y2") (pin "4") (pinfunction "151_4") (pintype "passive"))
    )
    (net (code "31") (name "Net-(D1-Pad1)") (class "Default")
      (node (ref "D1") (pin "1") (pinfunction "1_1") (pintype "passive"))
      (node (ref "R5") (pin "2") (pinfunction "2_2") (pintype "passive"))
    )
    (net (code "32") (name "Net-(FL1-IN)") (class "Default")
      (node (ref "FL1") (pin "1") (pinfunction "IN_1") (pintype "input"))
      (node (ref "U1") (pin "31") (pinfunction "RF_BG_31") (pintype "passive"))
    )
    (net (code "33") (name "Net-(FL1-OUT)") (class "Default")
      (node (ref "FL1") (pin "3") (pinfunction "OUT_3") (pintype "output"))
      (node (ref "J4") (pin "1") (pinfunction "1_1") (pintype "passive"))
    )
    (net (code "34") (name "Net-(G1-G)") (class "Default")
      (node (ref "G1") (pin "1") (pinfunction "G_1") (pintype "passive"))
      (node (ref "R14") (pin "2") (pinfunction "2_2") (pintype "passive"))
    )
    (net (code "35") (name "Net-(G1-S)") (class "Default")
      (node (ref "G1") (pin "2") (pinfunction "S_2") (pintype "passive"))
      (node (ref "H4") (pin "1") (pinfunction "1_1") (pintype "passive"))
    )
    (net (code "36") (name "Net-(G2-G)") (class "Default")
      (node (ref "G2") (pin "1") (pinfunction "G_1") (pintype "passive"))
      (node (ref "R15") (pin "2") (pinfunction "2_2") (pintype "passive"))
    )
    (net (code "37") (name "Net-(G2-S)") (class "Default")
      (node (ref "G2") (pin "2") (pinfunction "S_2") (pintype "passive"))
      (node (ref "H5") (pin "1") (pinfunction "1_1") (pintype "passive"))
    )
    (net (code "38") (name "Net-(G3-G)") (class "Default")
      (node (ref "G3") (pin "1") (pinfunction "G_1") (pintype "passive"))
      (node (ref "R16") (pin "2") (pinfunction "2_2") (pintype "passive"))
    )
    (net (code "39") (name "Net-(G3-S)") (class "Default")
      (node (ref "G3") (pin "2") (pinfunction "S_2") (pintype "passive"))
      (node (ref "H6") (pin "1") (pinfunction "1_1") (pintype "passive"))
    )
    (net (code "40") (name "Net-(G4-G)") (class "Default")
      (node (ref "G4") (pin "1") (pinfunction "G_1") (pintype "passive"))
      (node (ref "R17") (pin "2") (pinfunction "2_2") (pintype "passive"))
    )
    (net (code "41") (name "Net-(G4-S)") (class "Default")
      (node (ref "G4") (pin "2") (pinfunction "S_2") (pintype "passive"))
      (node (ref "H7") (pin "1") (pinfunction "1_1") (pintype "passive"))
    )
    (net (code "42") (name "Net-(H1-Pad2)") (class "Default")
      (node (ref "H1") (pin "2") (pinfunction "2_2") (pintype "passive"))
      (node (ref "S1") (pin "1") (pinfunction "1_1") (pintype "passive"))
    )
    (net (code "43") (name "Net-(H2-Pad3)") (class "Default")
      (node (ref "H2") (pin "3") (pinfunction "3_3") (pintype "passive"))
      (node (ref "J1") (pin "3") (pinfunction "3_3") (pintype "passive"))
    )
    (net (code "44") (name "Net-(H2-Pad4)") (class "Default")
      (node (ref "H2") (pin "4") (pinfunction "4_4") (pintype "passive"))
      (node (ref "J2") (pin "3") (pinfunction "3_3") (pintype "passive"))
    )
    (net (code "45") (name "Net-(J3-Pad1)") (class "Default")
      (node (ref "J3") (pin "1") (pinfunction "1_1") (pintype "passive"))
      (node (ref "R25") (pin "1") (pinfunction "1_1") (pintype "passive"))
      (node (ref "R28") (pin "2") (pinfunction "2_2") (pintype "passive"))
    )
    (net (code "46") (name "Net-(J4-Pad2)") (class "Default")
      (node (ref "J4") (pin "2") (pinfunction "2_2") (pintype "passive"))
      (node (ref "L2") (pin "2") (pinfunction "2_2") (pintype "passive"))
    )
    (net (code "47") (name "Net-(R13-Pad1)") (class "Default")
      (node (ref "R13") (pin "1") (pinfunction "1_1") (pintype "passive"))
      (node (ref "S2") (pin "2") (pinfunction "2_2") (pintype "passive"))
    )
    (net (code "48") (name "Net-(U1-DCDC_ANA_SW)") (class "Default")
      (node (ref "L1") (pin "2") (pinfunction "2_2") (pintype "passive"))
      (node (ref "U1") (pin "38") (pinfunction "DCDC_ANA_SW_38") (pintype "passive"))
    )
    (net (code "49") (name "Net-(U1-DCDC_DIG_SW)") (class "Default")
      (node (ref "L4") (pin "2") (pinfunction "2_2") (pintype "passive"))
      (node (ref "U1") (pin "43") (pinfunction "DCDC_DIG_SW_43") (pintype "passive"))
    )
    (net (code "50") (name "Net-(U1-DCDC_PA_OUT)") (class "Default")
      (node (ref "C18") (pin "2") (pinfunction "2_2") (pintype "passive"))
      (node (ref "C19") (pin "2") (pinfunction "2_2") (pintype "passive"))
      (node (ref "C20") (pin "2") (pinfunction "2_2") (pintype "passive"))
      (node (ref "U1") (pin "33") (pinfunction "VDD_PA_IN_33") (pintype "passive"))
      (node (ref "U1") (pin "42") (pinfunction "DCDC_PA_OUT_42") (pintype "passive"))
    )
    (net (code "51") (name "Net-(U1-DCDC_PA_SW_N)") (class "Default")
      (node (ref "L3") (pin "1") (pinfunction "1_1") (pintype "passive"))
      (node (ref "U1") (pin "41") (pinfunction "DCDC_PA_SW_N_41") (pintype "passive"))
    )
    (net (code "52") (name "Net-(U1-DCDC_PA_SW_P)") (class "Default")
      (node (ref "L3") (pin "2") (pinfunction "2_2") (pintype "passive"))
      (node (ref "U1") (pin "40") (pinfunction "DCDC_PA_SW_P_40") (pintype "passive"))
    )
    (net (code "53") (name "Net-(U1-GPIO_23{slash}JTAG_TDI)") (class "Default")
      (node (ref "R21") (pin "1") (pinfunction "1_1") (pintype "passive"))
      (node (ref "U1") (pin "16") (pinfunction "GPIO_23/JTAG_TDI_16") (pintype "passive"))
    )
    (net (code "54") (name "Net-(U1-GPIO_24{slash}JTAG_TDO)") (class "Default")
      (node (ref "R19") (pin "1") (pinfunction "1_1") (pintype "passive"))
      (node (ref "U1") (pin "17") (pinfunction "GPIO_24/JTAG_TDO_17") (pintype "passive"))
    )
    (net (code "55") (name "Net-(U1-GPIO_25{slash}SOP2)") (class "Default")
      (node (ref "J3") (pin "2") (pinfunction "2_2") (pintype "passive"))
      (node (ref "U1") (pin "21") (pinfunction "GPIO_25/SOP2_21") (pintype "passive"))
    )
    (net (code "56") (name "Net-(U1-GPIO_29{slash}JTAG_TMS)") (class "Default")
      (node (ref "R23") (pin "1") (pinfunction "1_1") (pintype "passive"))
      (node (ref "U1") (pin "20") (pinfunction "GPIO_29/JTAG_TMS_20") (pintype "passive"))
    )
    (net (code "57") (name "Net-(U1-LDO_IN1)") (class "Default")
      (node (ref "C15") (pin "2") (pinfunction "2_2") (pintype "passive"))
      (node (ref "C8") (pin "2") (pinfunction "2_2") (pintype "passive"))
      (node (ref "C9") (pin "2") (pinfunction "2_2") (pintype "passive"))
      (node (ref "L1") (pin "1") (pinfunction "1_1") (pintype "passive"))
      (node (ref "U1") (pin "25") (pinfunction "LDO_IN2_25") (pintype "passive"))
      (node (ref "U1") (pin "36") (pinfunction "LDO_IN1_36") (pintype "passive"))
      (node (ref "U1") (pin "48") (pinfunction "VDD_ANA1_48") (pintype "passive"))
    )
    (net (code "58") (name "Net-(U1-RTC_XTAL_N)") (class "Default")
      (node (ref "C35") (pin "2") (pinfunction "2_2") (pintype "passive"))
      (node (ref "U1") (pin "52") (pinfunction "RTC_XTAL_N_52") (pintype "passive"))
      (node (ref "Y1") (pin "2") (pinfunction "2_2") (pintype "passive"))
    )
    (net (code "59") (name "Net-(U1-RTC_XTAL_P)") (class "Default")
      (node (ref "C36") (pin "2") (pinfunction "2_2") (pintype "passive"))
      (node (ref "U1") (pin "51") (pinfunction "RTC_XTAL_P_51") (pintype "passive"))
      (node (ref "Y1") (pin "1") (pinfunction "1_1") (pintype "passive"))
    )
    (net (code "60") (name "Net-(U1-SOP0)") (class "Default")
      (node (ref "R18") (pin "2") (pinfunction "2_2") (pintype "passive"))
      (node (ref "U1") (pin "35") (pinfunction "SOP0_35") (pintype "passive"))
    )
    (net (code "61") (name "Net-(U1-SOP1)") (class "Default")
      (node (ref "R20") (pin "2") (pinfunction "2_2") (pintype "passive"))
      (node (ref "U1") (pin "34") (pinfunction "SOP1_34") (pintype "passive"))
    )
    (net (code "62") (name "Net-(U1-VDD_DIG1)") (class "Default")
      (node (ref "C23") (pin "2") (pinfunction "2_2") (pintype "passive"))
      (node (ref "C24") (pin "2") (pinfunction "2_2") (pintype "passive"))
      (node (ref "C25") (pin "2") (pinfunction "2_2") (pintype "passive"))
      (node (ref "L4") (pin "1") (pinfunction "1_1") (pintype "passive"))
      (node (ref "U1") (pin "56") (pinfunction "VDD_DIG2_56") (pintype "passive"))
      (node (ref "U1") (pin "9") (pinfunction "VDD_DIG1_9") (pintype "passive"))
    )
    (net (code "63") (name "Net-(U1-VDD_PLL)") (class "Default")
      (node (ref "C30") (pin "2") (pinfunction "2_2") (pintype "passive"))
      (node (ref "U1") (pin "24") (pinfunction "VDD_PLL_24") (pintype "passive"))
    )
    (net (code "64") (name "Net-(U1-VDD_RAM)") (class "Default")
      (node (ref "C29") (pin "2") (pinfunction "2_2") (pintype "passive"))
      (node (ref "U1") (pin "49") (pinfunction "VDD_RAM_49") (pintype "passive"))
    )
    (net (code "65") (name "Net-(U1-VIN_DCDC_ANA)") (class "Default")
      (node (ref "C1") (pin "2") (pinfunction "2_2") (pintype "passive"))
      (node (ref "C3") (pin "2") (pinfunction "2_2") (pintype "passive"))
      (node (ref "C4") (pin "2") (pinfunction "2_2") (pintype "passive"))
      (node (ref "C5") (pin "2") (pinfunction "2_2") (pintype "passive"))
      (node (ref "U1") (pin "10") (pinfunction "VIN_IO1_10") (pintype "passive"))
      (node (ref "U1") (pin "37") (pinfunction "VIN_DCDC_ANA_37") (pintype "passive"))
      (node (ref "U1") (pin "39") (pinfunction "VIN_DCDC_PA_39") (pintype "passive"))
      (node (ref "U1") (pin "44") (pinfunction "VIN_DCDC_DIG_44") (pintype "passive"))
      (node (ref "U1") (pin "54") (pinfunction "VIN_IO2_54") (pintype "passive"))
    )
    (net (code "66") (name "Net-(U1-WLAN_XTALM)") (class "Default")
      (node (ref "C37") (pin "2") (pinfunction "2_2") (pintype "passive"))
      (node (ref "U1") (pin "22") (pinfunction "WLAN_XTALM_22") (pintype "passive"))
      (node (ref "Y2") (pin "3") (pinfunction "149_3") (pintype "passive"))
    )
    (net (code "67") (name "Net-(U1-WLAN_XTALP)") (class "Default")
      (node (ref "C38") (pin "2") (pinfunction "2_2") (pintype "passive"))
      (node (ref "U1") (pin "23") (pinfunction "WLAN_XTALP_23") (pintype "passive"))
      (node (ref "Y2") (pin "1") (pinfunction "148_1") (pintype "passive"))
    )
    (net (code "68") (name "Net-(U5-CPOUT)") (class "Default")
      (node (ref "C11") (pin "2") (pinfunction "2_2") (pintype "passive"))
      (node (ref "U5") (pin "20") (pinfunction "CPOUT_20") (pintype "passive"))
    )
    (net (code "69") (name "Net-(U5-REGOUT)") (class "Default")
      (node (ref "C12") (pin "2") (pinfunction "2_2") (pintype "passive"))
      (node (ref "U5") (pin "10") (pinfunction "REGOUT_10") (pintype "passive"))
    )
    (net (code "70") (name "Net-(U6-FB)") (class "Default")
      (node (ref "C17") (pin "1") (pinfunction "1_1") (pintype "passive"))
      (node (ref "R6") (pin "1") (pinfunction "1_1") (pintype "passive"))
      (node (ref "R9") (pin "2") (pinfunction "2_2") (pintype "passive"))
      (node (ref "U6") (pin "5") (pinfunction "FB_5") (pintype "passive"))
    )
    (net (code "71") (name "Net-(U7-L)") (class "Default")
      (node (ref "L5") (pin "2") (pinfunction "2_2") (pintype "passive"))
      (node (ref "U7") (pin "5") (pinfunction "L_5") (pintype "passive"))
    )
    (net (code "72") (name "VCC_3V3") (class "Default")
      (node (ref "C16") (pin "2") (pinfunction "2_2") (pintype "passive"))
      (node (ref "C17") (pin "2") (pinfunction "2_2") (pintype "passive"))
      (node (ref "C2") (pin "2") (pinfunction "2_2") (pintype "passive"))
      (node (ref "C22") (pin "2") (pinfunction "2_2") (pintype "passive"))
      (node (ref "C32") (pin "2") (pinfunction "2_2") (pintype "passive"))
      (node (ref "L5") (pin "1") (pinfunction "1_1") (pintype "passive"))
      (node (ref "R1") (pin "2") (pinfunction "2_2") (pintype "passive"))
      (node (ref "R11") (pin "2") (pinfunction "2_2") (pintype "passive"))
      (node (ref "R25") (pin "2") (pinfunction "2_2") (pintype "passive"))
      (node (ref "R4") (pin "1") (pinfunction "1_1") (pintype "passive"))
      (node (ref "R6") (pin "2") (pinfunction "2_2") (pintype "passive"))
      (node (ref "U2") (pin "3") (pinfunction "WP_3") (pintype "passive"))
      (node (ref "U2") (pin "7") (pinfunction "RESET_7") (pintype "passive"))
      (node (ref "U2") (pin "8") (pinfunction "VCC_8") (pintype "passive"))
      (node (ref "U6") (pin "4") (pinfunction "OUT_4") (pintype "passive"))
      (node (ref "U7") (pin "1") (pinfunction "VIN_1") (pintype "passive"))
      (node (ref "U7") (pin "3") (pinfunction "EN_3") (pintype "passive"))
    )
    (net (code "73") (name "VCC_BRD") (class "Default")
      (node (ref "C21") (pin "2") (pinfunction "2_2") (pintype "passive"))
      (node (ref "G1") (pin "3") (pinfunction "D_3") (pintype "passive"))
      (node (ref "G2") (pin "3") (pinfunction "D_3") (pintype "passive"))
      (node (ref "G3") (pin "3") (pinfunction "D_3") (pintype "passive"))
      (node (ref "G4") (pin "3") (pinfunction "D_3") (pintype "passive"))
      (node (ref "H2") (pin "1") (pinfunction "1_1") (pintype "passive"))
      (node (ref "H3") (pin "16") (pinfunction "16_16") (pintype "passive"))
      (node (ref "R5") (pin "1") (pinfunction "1_1") (pintype "passive"))
      (node (ref "S1") (pin "2") (pinfunction "2_2") (pintype "passive"))
      (node (ref "U6") (pin "1") (pinfunction "EN_1") (pintype "passive"))
      (node (ref "U6") (pin "2") (pinfunction "IN_2") (pintype "passive"))
    )
    (net (code "74") (name "VCC_DCDC_3V3") (class "Default")
      (node (ref "C13") (pin "2") (pinfunction "2_2") (pintype "passive"))
      (node (ref "C28") (pin "2") (pinfunction "2_2") (pintype "passive"))
      (node (ref "C31") (pin "2") (pinfunction "2_2") (pintype "passive"))
      (node (ref "C7") (pin "1") (pinfunction "1_1") (pintype "passive"))
      (node (ref "R2") (pin "2") (pinfunction "2_2") (pintype "passive"))
      (node (ref "R3") (pin "2") (pinfunction "2_2") (pintype "passive"))
      (node (ref "U1") (pin "47") (pinfunction "VDD_ANA2_47") (pintype "passive"))
      (node (ref "U5") (pin "13") (pinfunction "VDD_13") (pintype "passive"))
      (node (ref "U5") (pin "3") (pintype "passive"))
      (node (ref "U5") (pin "8") (pinfunction "VLOGIC_8") (pintype "passive"))
      (node (ref "U7") (pin "4") (pinfunction "OUT_4") (pintype "passive"))
    )
    (net (code "75") (name "unconnected-(C14-Pad2)") (class "Default")
      (node (ref "C14") (pin "2") (pinfunction "2_2") (pintype "passive"))
    )
    (net (code "76") (name "unconnected-(U1-DCDC_ANA2_SW_N-Pad46)") (class "Default")
      (node (ref "U1") (pin "46") (pinfunction "DCDC_ANA2_SW_N_46") (pintype "passive"))
    )
    (net (code "77") (name "unconnected-(U1-GPIO_00-Pad50)") (class "Default")
      (node (ref "U1") (pin "50") (pinfunction "GPIO_00_50") (pintype "passive"))
    )
    (net (code "78") (name "unconnected-(U1-GPIO_07-Pad62)") (class "Default")
      (node (ref "U1") (pin "62") (pinfunction "GPIO_07_62") (pintype "passive"))
    )
    (net (code "79") (name "unconnected-(U1-GPIO_08-Pad63)") (class "Default")
      (node (ref "U1") (pin "63") (pinfunction "GPIO_08_63") (pintype "passive"))
    )
    (net (code "80") (name "unconnected-(U1-GPIO_22-Pad15)") (class "Default")
      (node (ref "U1") (pin "15") (pinfunction "GPIO_22_15") (pintype "passive"))
    )
    (net (code "81") (name "unconnected-(U1-GPIO_28-Pad18)") (class "Default")
      (node (ref "U1") (pin "18") (pinfunction "GPIO_28_18") (pintype "passive"))
    )
    (net (code "82") (name "unconnected-(U1-NC_26-Pad26)") (class "Default")
      (node (ref "U1") (pin "26") (pinfunction "NC_26_26") (pintype "passive"))
    )
    (net (code "83") (name "unconnected-(U1-NC_27-Pad27)") (class "Default")
      (node (ref "U1") (pin "27") (pinfunction "NC_27_27") (pintype "passive"))
    )
    (net (code "84") (name "unconnected-(U1-NC_28-Pad28)") (class "Default")
      (node (ref "U1") (pin "28") (pinfunction "NC_28_28") (pintype "passive"))
    )
    (net (code "85") (name "unconnected-(U5-AD0-Pad9)") (class "Default")
      (node (ref "U5") (pin "9") (pinfunction "AD0_9") (pintype "passive"))
    )
    (net (code "86") (name "unconnected-(U5-AUX_CL-Pad7)") (class "Default")
      (node (ref "U5") (pin "7") (pinfunction "AUX_CL_7") (pintype "passive"))
    )
    (net (code "87") (name "unconnected-(U5-AUX_DA-Pad6)") (class "Default")
      (node (ref "U5") (pin "6") (pinfunction "AUX_DA_6") (pintype "passive"))
    )
    (net (code "88") (name "unconnected-(U5-CLKOUT-Pad22)") (class "Default")
      (node (ref "U5") (pin "22") (pinfunction "CLKOUT_22") (pintype "passive"))
    )
    (net (code "89") (name "unconnected-(U5-GND-Pad18)") (class "Default")
      (node (ref "U5") (pin "18") (pinfunction "GND_18") (pintype "passive"))
    )
    (net (code "90") (name "unconnected-(U5-INT-Pad12)") (class "Default")
      (node (ref "U5") (pin "12") (pinfunction "INT_12") (pintype "passive"))
    )
    (net (code "91") (name "unconnected-(U5-RESV-Pad19)") (class "Default")
      (node (ref "U5") (pin "19") (pinfunction "RESV_19") (pintype "passive"))
    )
    (net (code "92") (name "unconnected-(U5-RESV-Pad21)") (class "Default")
      (node (ref "U5") (pin "21") (pinfunction "RESV_21") (pintype "passive"))
    )
  )
)
